# untitled.net
KiCad netlist of a schematic drawn in EAGLE
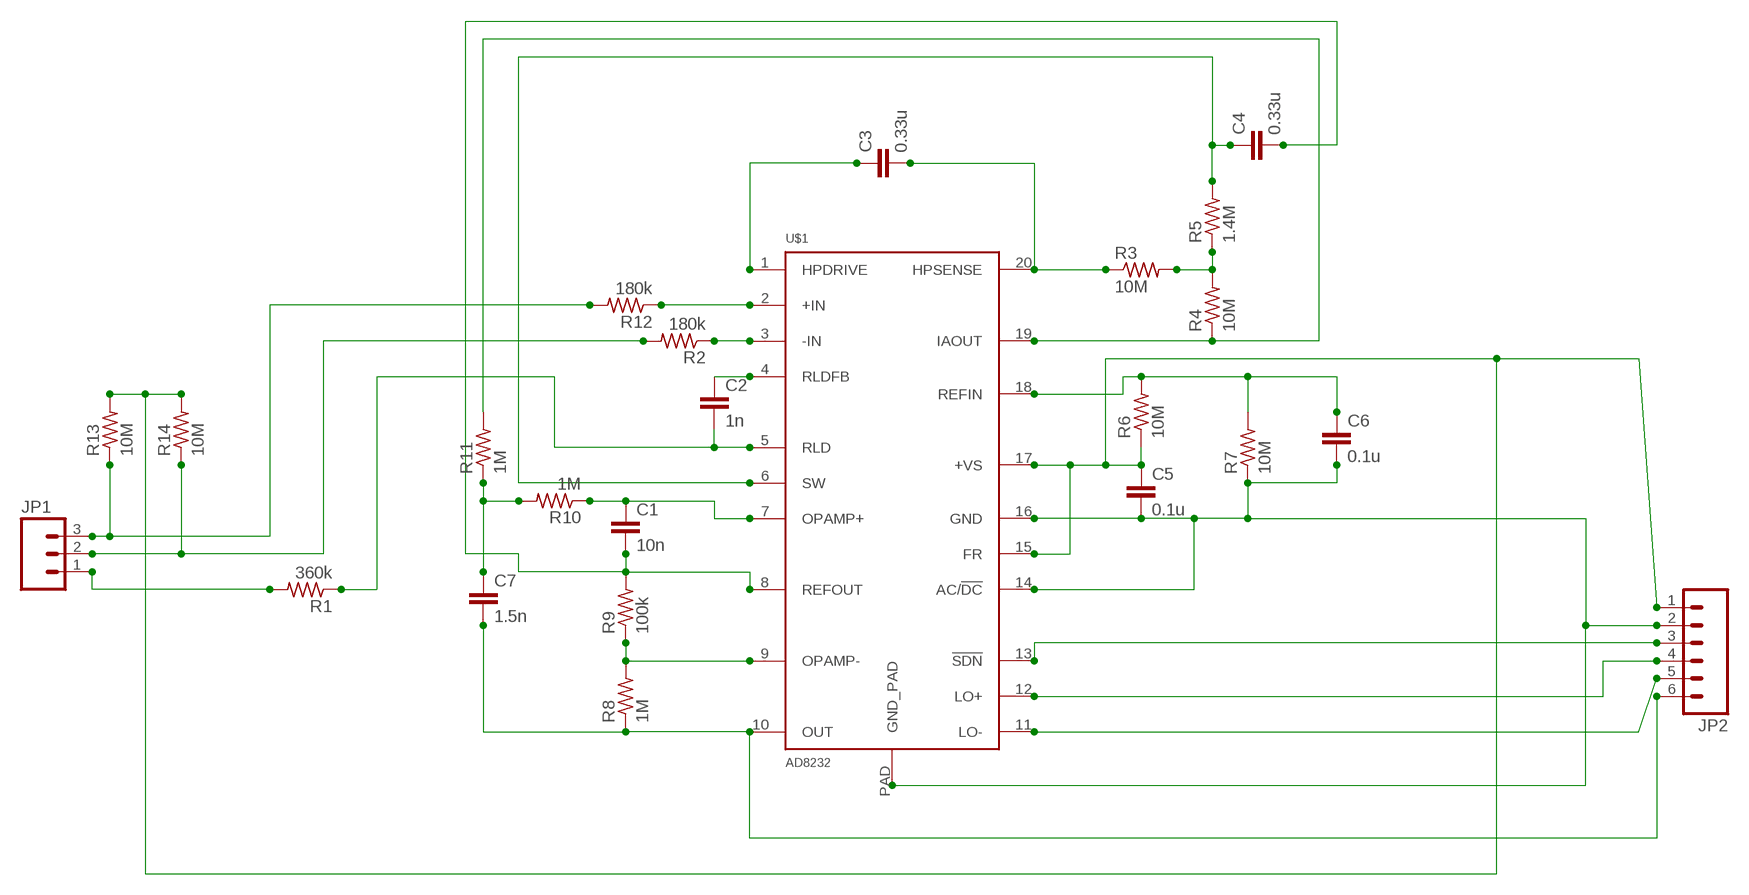
[diagram p0: schematic, sheet 1]

(export (version "E")
  (design (tool "Eeschema 10.0.6"))
  (components
    (comp (ref "C1")
      (value "10n")
      (footprint "eagle-import:C0603")
      (libsource (lib "eagle-import") (part "C-EUC0603"))
    )
    (comp (ref "C2")
      (value "1n")
      (footprint "eagle-import:C0603")
      (libsource (lib "eagle-import") (part "C-EUC0603"))
    )
    (comp (ref "C3")
      (value "0.33u")
      (footprint "eagle-import:C0603")
      (libsource (lib "eagle-import") (part "C-EUC0603"))
    )
    (comp (ref "C4")
      (value "0.33u")
      (footprint "eagle-import:C0603")
      (libsource (lib "eagle-import") (part "C-EUC0603"))
    )
    (comp (ref "C5")
      (value "0.1u")
      (footprint "eagle-import:C0603")
      (libsource (lib "eagle-import") (part "C-EUC0603"))
    )
    (comp (ref "C6")
      (value "0.1u")
      (footprint "eagle-import:C0603")
      (libsource (lib "eagle-import") (part "C-EUC0603"))
    )
    (comp (ref "C7")
      (value "1.5n")
      (footprint "eagle-import:C0603")
      (libsource (lib "eagle-import") (part "C-EUC0603"))
    )
    (comp (ref "JP1")
      (value "M03PTH")
      (footprint "eagle-import:1X03")
      (libsource (lib "eagle-import") (part "M03PTH"))
    )
    (comp (ref "JP2")
      (value "M06SILK_FEMALE_PTH")
      (footprint "eagle-import:1X06")
      (libsource (lib "eagle-import") (part "M06SILK_FEMALE_PTH"))
    )
    (comp (ref "R1")
      (value "360k")
      (footprint "eagle-import:R0603")
      (libsource (lib "eagle-import") (part "R-US_R0603"))
    )
    (comp (ref "R2")
      (value "180k")
      (footprint "eagle-import:R0603")
      (libsource (lib "eagle-import") (part "R-US_R0603"))
    )
    (comp (ref "R3")
      (value "10M")
      (footprint "eagle-import:R0603")
      (libsource (lib "eagle-import") (part "R-US_R0603"))
    )
    (comp (ref "R4")
      (value "10M")
      (footprint "eagle-import:R0603")
      (libsource (lib "eagle-import") (part "R-US_R0603"))
    )
    (comp (ref "R5")
      (value "1.4M")
      (footprint "eagle-import:R0603")
      (libsource (lib "eagle-import") (part "R-US_R0603"))
    )
    (comp (ref "R6")
      (value "10M")
      (footprint "eagle-import:R0603")
      (libsource (lib "eagle-import") (part "R-US_R0603"))
    )
    (comp (ref "R7")
      (value "10M")
      (footprint "eagle-import:R0603")
      (libsource (lib "eagle-import") (part "R-US_R0603"))
    )
    (comp (ref "R8")
      (value "1M")
      (footprint "eagle-import:R0603")
      (libsource (lib "eagle-import") (part "R-US_R0603"))
    )
    (comp (ref "R9")
      (value "100k")
      (footprint "eagle-import:R0603")
      (libsource (lib "eagle-import") (part "R-US_R0603"))
    )
    (comp (ref "R10")
      (value "1M")
      (footprint "eagle-import:R0603")
      (libsource (lib "eagle-import") (part "R-US_R0603"))
    )
    (comp (ref "R11")
      (value "1M")
      (footprint "eagle-import:R0603")
      (libsource (lib "eagle-import") (part "R-US_R0603"))
    )
    (comp (ref "R12")
      (value "180k")
      (footprint "eagle-import:R0603")
      (libsource (lib "eagle-import") (part "R-US_R0603"))
    )
    (comp (ref "R13")
      (value "10M")
      (footprint "eagle-import:R0603")
      (libsource (lib "eagle-import") (part "R-US_R0603"))
    )
    (comp (ref "R14")
      (value "10M")
      (footprint "eagle-import:R0603")
      (libsource (lib "eagle-import") (part "R-US_R0603"))
    )
    (comp (ref "U$1")
      (value "AD8232")
      (footprint "eagle-import:LFCSP_20")
      (libsource (lib "eagle-import") (part "AD8232"))
    )
  )
  (nets
    (net (code "1") (name "Net-(C7-Pad1)") (class "Default")
      (node (ref "C7") (pin "1") (pinfunction "1_1") (pintype "passive"))
      (node (ref "R10") (pin "2") (pinfunction "2_2") (pintype "passive"))
      (node (ref "R11") (pin "1") (pinfunction "1_1") (pintype "passive"))
    )
    (net (code "2") (name "Net-(JP1-Pad1)") (class "Default")
      (node (ref "JP1") (pin "1") (pinfunction "1_1") (pintype "passive"))
      (node (ref "R1") (pin "2") (pinfunction "2_2") (pintype "passive"))
    )
    (net (code "3") (name "Net-(JP1-Pad2)") (class "Default")
      (node (ref "JP1") (pin "2") (pinfunction "2_2") (pintype "passive"))
      (node (ref "R14") (pin "1") (pinfunction "1_1") (pintype "passive"))
      (node (ref "R2") (pin "2") (pinfunction "2_2") (pintype "passive"))
    )
    (net (code "4") (name "Net-(JP1-Pad3)") (class "Default")
      (node (ref "JP1") (pin "3") (pinfunction "3_3") (pintype "passive"))
      (node (ref "R12") (pin "2") (pinfunction "2_2") (pintype "passive"))
      (node (ref "R13") (pin "1") (pinfunction "1_1") (pintype "passive"))
    )
    (net (code "5") (name "Net-(R3-Pad2)") (class "Default")
      (node (ref "R3") (pin "2") (pinfunction "2_2") (pintype "passive"))
      (node (ref "R4") (pin "2") (pinfunction "2_2") (pintype "passive"))
      (node (ref "R5") (pin "1") (pinfunction "1_1") (pintype "passive"))
    )
    (net (code "6") (name "Net-(U$1-+IN)") (class "Default")
      (node (ref "R12") (pin "1") (pinfunction "1_1") (pintype "passive"))
      (node (ref "U$1") (pin "2") (pinfunction "+IN_2") (pintype "bidirectional"))
    )
    (net (code "7") (name "Net-(U$1-+VS)") (class "Default")
      (node (ref "C5") (pin "1") (pinfunction "1_1") (pintype "passive"))
      (node (ref "JP2") (pin "1") (pinfunction "1_1") (pintype "passive"))
      (node (ref "R13") (pin "2") (pinfunction "2_2") (pintype "passive"))
      (node (ref "R14") (pin "2") (pinfunction "2_2") (pintype "passive"))
      (node (ref "R6") (pin "1") (pinfunction "1_1") (pintype "passive"))
      (node (ref "U$1") (pin "15") (pinfunction "FR_15") (pintype "bidirectional"))
      (node (ref "U$1") (pin "17") (pinfunction "+VS_17") (pintype "bidirectional"))
    )
    (net (code "8") (name "Net-(U$1--IN)") (class "Default")
      (node (ref "R2") (pin "1") (pinfunction "1_1") (pintype "passive"))
      (node (ref "U$1") (pin "3") (pinfunction "-IN_3") (pintype "bidirectional"))
    )
    (net (code "9") (name "Net-(U$1-AC{slash}~{DC})") (class "Default")
      (node (ref "C5") (pin "2") (pinfunction "2_2") (pintype "passive"))
      (node (ref "C6") (pin "2") (pinfunction "2_2") (pintype "passive"))
      (node (ref "JP2") (pin "2") (pinfunction "2_2") (pintype "passive"))
      (node (ref "R7") (pin "1") (pinfunction "1_1") (pintype "passive"))
      (node (ref "U$1") (pin "14") (pinfunction "AC/~{DC}_14") (pintype "bidirectional"))
      (node (ref "U$1") (pin "16") (pinfunction "GND_16") (pintype "bidirectional"))
      (node (ref "U$1") (pin "PAD") (pinfunction "GND_PAD_PAD") (pintype "bidirectional"))
    )
    (net (code "10") (name "Net-(U$1-HPDRIVE)") (class "Default")
      (node (ref "C3") (pin "1") (pinfunction "1_1") (pintype "passive"))
      (node (ref "U$1") (pin "1") (pinfunction "HPDRIVE_1") (pintype "bidirectional"))
    )
    (net (code "11") (name "Net-(U$1-HPSENSE)") (class "Default")
      (node (ref "C3") (pin "2") (pinfunction "2_2") (pintype "passive"))
      (node (ref "R3") (pin "1") (pinfunction "1_1") (pintype "passive"))
      (node (ref "U$1") (pin "20") (pinfunction "HPSENSE_20") (pintype "bidirectional"))
    )
    (net (code "12") (name "Net-(U$1-IAOUT)") (class "Default")
      (node (ref "R11") (pin "2") (pinfunction "2_2") (pintype "passive"))
      (node (ref "R4") (pin "1") (pinfunction "1_1") (pintype "passive"))
      (node (ref "U$1") (pin "19") (pinfunction "IAOUT_19") (pintype "bidirectional"))
    )
    (net (code "13") (name "Net-(U$1-LO+)") (class "Default")
      (node (ref "JP2") (pin "4") (pinfunction "4_4") (pintype "passive"))
      (node (ref "U$1") (pin "12") (pinfunction "LO+_12") (pintype "bidirectional"))
    )
    (net (code "14") (name "Net-(U$1-LO-)") (class "Default")
      (node (ref "JP2") (pin "5") (pinfunction "5_5") (pintype "passive"))
      (node (ref "U$1") (pin "11") (pinfunction "LO-_11") (pintype "bidirectional"))
    )
    (net (code "15") (name "Net-(U$1-OPAMP+)") (class "Default")
      (node (ref "C1") (pin "1") (pinfunction "1_1") (pintype "passive"))
      (node (ref "R10") (pin "1") (pinfunction "1_1") (pintype "passive"))
      (node (ref "U$1") (pin "7") (pinfunction "OPAMP+_7") (pintype "bidirectional"))
    )
    (net (code "16") (name "Net-(U$1-OPAMP-)") (class "Default")
      (node (ref "R8") (pin "2") (pinfunction "2_2") (pintype "passive"))
      (node (ref "R9") (pin "1") (pinfunction "1_1") (pintype "passive"))
      (node (ref "U$1") (pin "9") (pinfunction "OPAMP-_9") (pintype "bidirectional"))
    )
    (net (code "17") (name "Net-(U$1-OUT)") (class "Default")
      (node (ref "C7") (pin "2") (pinfunction "2_2") (pintype "passive"))
      (node (ref "JP2") (pin "6") (pinfunction "6_6") (pintype "passive"))
      (node (ref "R8") (pin "1") (pinfunction "1_1") (pintype "passive"))
      (node (ref "U$1") (pin "10") (pinfunction "OUT_10") (pintype "bidirectional"))
    )
    (net (code "18") (name "Net-(U$1-REFIN)") (class "Default")
      (node (ref "C6") (pin "1") (pinfunction "1_1") (pintype "passive"))
      (node (ref "R6") (pin "2") (pinfunction "2_2") (pintype "passive"))
      (node (ref "R7") (pin "2") (pinfunction "2_2") (pintype "passive"))
      (node (ref "U$1") (pin "18") (pinfunction "REFIN_18") (pintype "bidirectional"))
    )
    (net (code "19") (name "Net-(U$1-REFOUT)") (class "Default")
      (node (ref "C1") (pin "2") (pinfunction "2_2") (pintype "passive"))
      (node (ref "C4") (pin "2") (pinfunction "2_2") (pintype "passive"))
      (node (ref "R9") (pin "2") (pinfunction "2_2") (pintype "passive"))
      (node (ref "U$1") (pin "8") (pinfunction "REFOUT_8") (pintype "bidirectional"))
    )
    (net (code "20") (name "Net-(U$1-RLD)") (class "Default")
      (node (ref "C2") (pin "2") (pinfunction "2_2") (pintype "passive"))
      (node (ref "R1") (pin "1") (pinfunction "1_1") (pintype "passive"))
      (node (ref "U$1") (pin "5") (pinfunction "RLD_5") (pintype "bidirectional"))
    )
    (net (code "21") (name "Net-(U$1-RLDFB)") (class "Default")
      (node (ref "C2") (pin "1") (pinfunction "1_1") (pintype "passive"))
      (node (ref "U$1") (pin "4") (pinfunction "RLDFB_4") (pintype "bidirectional"))
    )
    (net (code "22") (name "Net-(U$1-SW)") (class "Default")
      (node (ref "C4") (pin "1") (pinfunction "1_1") (pintype "passive"))
      (node (ref "R5") (pin "2") (pinfunction "2_2") (pintype "passive"))
      (node (ref "U$1") (pin "6") (pinfunction "SW_6") (pintype "bidirectional"))
    )
    (net (code "23") (name "Net-(U$1-~{SDN})") (class "Default")
      (node (ref "JP2") (pin "3") (pinfunction "3_3") (pintype "passive"))
      (node (ref "U$1") (pin "13") (pinfunction "~{SDN}_13") (pintype "bidirectional"))
    )
  )
)
